# connectors.net
KiCad netlist of a schematic drawn in EAGLE
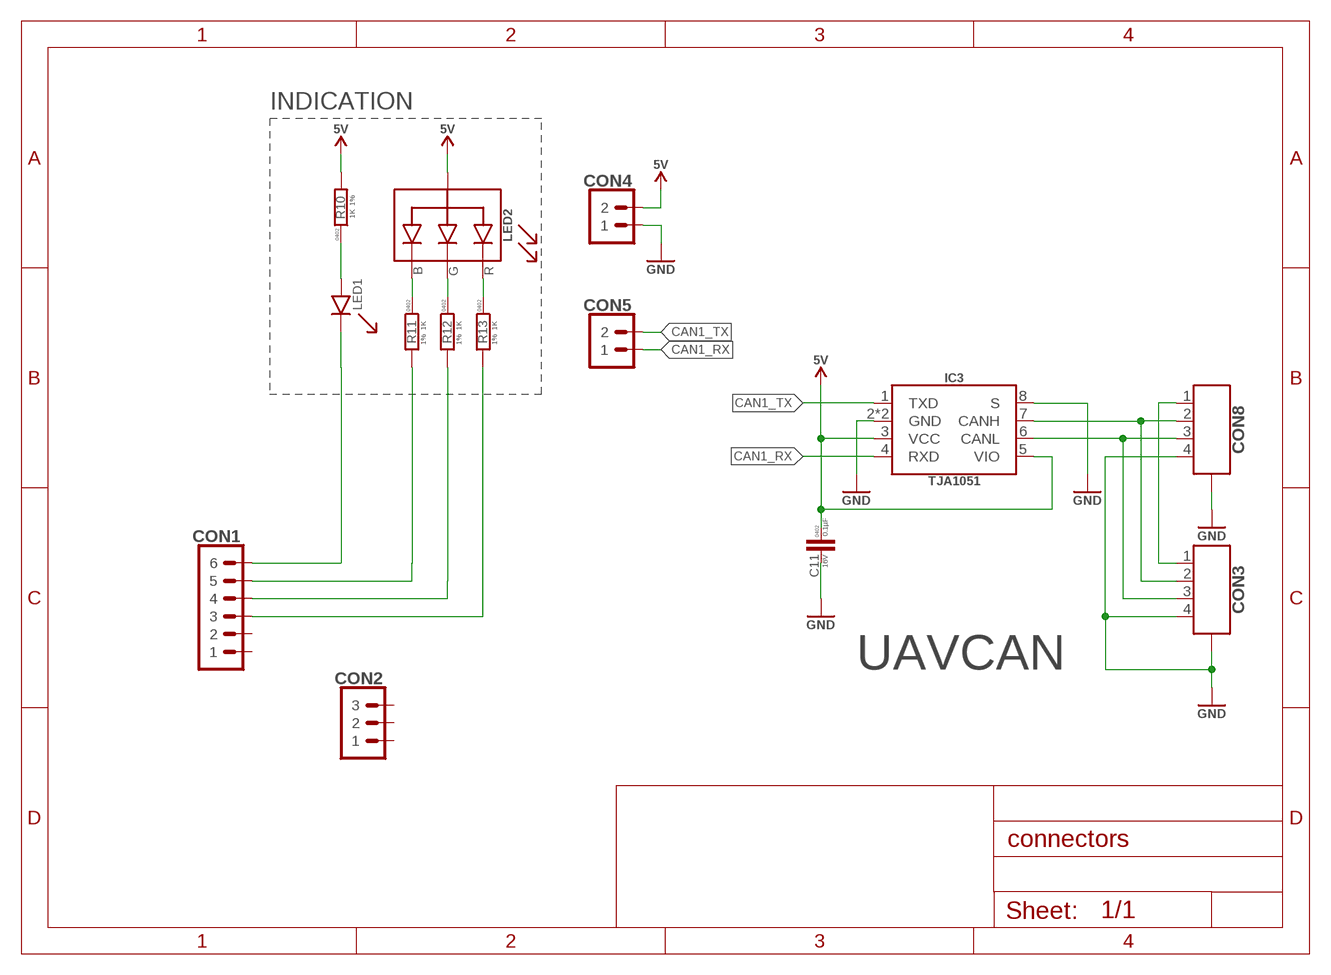
[diagram p0: schematic, sheet 1]

(export (version "E")
  (design (tool "Eeschema 10.0.6"))
  (components
    (comp (ref "C11")
      (value "0.1µF")
      (footprint "eagle-import:C0402")
      (fields
        (field (name "MANF") "Murata Electronics North America")
        (field (name "PACKAGE") "0402")
        (field (name "TOLERANCE") "+-10%")
        (field (name "VOLTAGE") "16V")
      )
      (libsource (lib "eagle-import") (part "0.1µF-0402-16V_10%_X7R"))
    )
    (comp (ref "CON1")
      (value "PINHEAD_1X06-2")
      (footprint "eagle-import:1X06-PTH-2")
      (libsource (lib "eagle-import") (part "PINHEAD_1X06-2"))
    )
    (comp (ref "CON2")
      (value "PINHEAD_1X03-2.54-RA")
      (footprint "eagle-import:1X03-PTH-2.54-RA")
      (libsource (lib "eagle-import") (part "PINHEAD_1X03-2.54-RA"))
    )
    (comp (ref "CON3")
      (value "CON-4P-JST_GH-RA")
      (footprint "eagle-import:JST_GH-4P-RA")
      (fields (field (name "MANF") "JST Sales America Inc"))
      (libsource (lib "eagle-import") (part "CON-4P-RA-JST_GH"))
    )
    (comp (ref "CON4")
      (value "PINHEAD_1X02-2")
      (footprint "eagle-import:1X02-PTH-2")
      (libsource (lib "eagle-import") (part "PINHEAD_1X02-2"))
    )
    (comp (ref "CON5")
      (value "PINHEAD_1X02-2")
      (footprint "eagle-import:1X02-PTH-2")
      (libsource (lib "eagle-import") (part "PINHEAD_1X02-2"))
    )
    (comp (ref "CON8")
      (value "CON-4P-JST_GH-RA")
      (footprint "eagle-import:JST_GH-4P-RA")
      (fields (field (name "MANF") "JST Sales America Inc"))
      (libsource (lib "eagle-import") (part "CON-4P-RA-JST_GH"))
    )
    (comp (ref "IC3")
      (value "TJA1051")
      (footprint "eagle-import:SOT782-1")
      (fields (field (name "MANF") "NXP Semiconductors"))
      (libsource (lib "eagle-import") (part "TJA1051"))
    )
    (comp (ref "LED1")
      (value "GREEN")
      (footprint "eagle-import:0402_LED")
      (fields (field (name "MANF") "Rohm Semiconductor"))
      (libsource (lib "eagle-import") (part "LED-0402-GREEN"))
    )
    (comp (ref "LED2")
      (value "LTST-C19HE1WT")
      (footprint "eagle-import:LITE_ON_RGB_LED")
      (fields (field (name "MANF") "Lite-On Inc"))
      (libsource (lib "eagle-import") (part "LTST-C19HE1WT"))
    )
    (comp (ref "R10")
      (value "1K")
      (footprint "eagle-import:R0402")
      (fields (field (name "MANF") "Yageo") (field (name "PACKAGE") "0402") (field (name "TOLERANCE") "1%"))
      (libsource (lib "eagle-import") (part "1K-0402-1%"))
    )
    (comp (ref "R11")
      (value "1K")
      (footprint "eagle-import:R0402")
      (fields (field (name "MANF") "Yageo") (field (name "PACKAGE") "0402") (field (name "TOLERANCE") "1%"))
      (libsource (lib "eagle-import") (part "1K-0402-1%"))
    )
    (comp (ref "R12")
      (value "1K")
      (footprint "eagle-import:R0402")
      (fields (field (name "MANF") "Yageo") (field (name "PACKAGE") "0402") (field (name "TOLERANCE") "1%"))
      (libsource (lib "eagle-import") (part "1K-0402-1%"))
    )
    (comp (ref "R13")
      (value "1K")
      (footprint "eagle-import:R0402")
      (fields (field (name "MANF") "Yageo") (field (name "PACKAGE") "0402") (field (name "TOLERANCE") "1%"))
      (libsource (lib "eagle-import") (part "1K-0402-1%"))
    )
  )
  (nets
    (net (code "1") (name "5V") (class "Default")
      (node (ref "C11") (pin "1") (pinfunction "1_1") (pintype "passive"))
      (node (ref "CON4") (pin "2") (pinfunction "2_2") (pintype "passive"))
      (node (ref "IC3") (pin "3") (pinfunction "VCC_3") (pintype "bidirectional"))
      (node (ref "IC3") (pin "5") (pinfunction "VIO_5") (pintype "bidirectional"))
      (node (ref "LED2") (pin "+") (pinfunction "A_+") (pintype "bidirectional"))
      (node (ref "R10") (pin "2") (pinfunction "2_2") (pintype "passive"))
    )
    (net (code "2") (name "CAN1_RX") (class "Default")
      (node (ref "CON5") (pin "1") (pinfunction "1_1") (pintype "passive"))
      (node (ref "IC3") (pin "4") (pinfunction "RXD_4") (pintype "bidirectional"))
    )
    (net (code "3") (name "CAN1_TX") (class "Default")
      (node (ref "CON5") (pin "2") (pinfunction "2_2") (pintype "passive"))
      (node (ref "IC3") (pin "1") (pinfunction "TXD_1") (pintype "bidirectional"))
    )
    (net (code "4") (name "GND") (class "Default")
      (node (ref "C11") (pin "2") (pinfunction "2_2") (pintype "passive"))
      (node (ref "CON3") (pin "4") (pinfunction "4_4") (pintype "bidirectional"))
      (node (ref "CON3") (pin "M$0") (pinfunction "GND_M$0") (pintype "bidirectional"))
      (node (ref "CON3") (pin "M$1") (pinfunction "GND_M$1") (pintype "bidirectional"))
      (node (ref "CON4") (pin "1") (pinfunction "1_1") (pintype "passive"))
      (node (ref "CON8") (pin "4") (pinfunction "4_4") (pintype "bidirectional"))
      (node (ref "CON8") (pin "M$0") (pinfunction "GND_M$0") (pintype "bidirectional"))
      (node (ref "CON8") (pin "M$1") (pinfunction "GND_M$1") (pintype "bidirectional"))
      (node (ref "IC3") (pin "2") (pinfunction "GND_2") (pintype "bidirectional"))
      (node (ref "IC3") (pin "8") (pinfunction "S_8") (pintype "bidirectional"))
      (node (ref "IC3") (pin "PAD") (pinfunction "GND_PAD") (pintype "bidirectional"))
    )
    (net (code "5") (name "Net-(CON1-Pad3)") (class "Default")
      (node (ref "CON1") (pin "3") (pinfunction "3_3") (pintype "passive"))
      (node (ref "R13") (pin "2") (pinfunction "2_2") (pintype "passive"))
    )
    (net (code "6") (name "Net-(CON1-Pad4)") (class "Default")
      (node (ref "CON1") (pin "4") (pinfunction "4_4") (pintype "passive"))
      (node (ref "R12") (pin "2") (pinfunction "2_2") (pintype "passive"))
    )
    (net (code "7") (name "Net-(CON1-Pad5)") (class "Default")
      (node (ref "CON1") (pin "5") (pinfunction "5_5") (pintype "passive"))
      (node (ref "R11") (pin "2") (pinfunction "2_2") (pintype "passive"))
    )
    (net (code "8") (name "Net-(CON1-Pad6)") (class "Default")
      (node (ref "CON1") (pin "6") (pinfunction "6_6") (pintype "passive"))
      (node (ref "LED1") (pin "C") (pinfunction "C_C") (pintype "bidirectional"))
    )
    (net (code "9") (name "Net-(CON3-Pad1)") (class "Default")
      (node (ref "CON3") (pin "1") (pinfunction "1_1") (pintype "bidirectional"))
      (node (ref "CON8") (pin "1") (pinfunction "1_1") (pintype "bidirectional"))
    )
    (net (code "10") (name "Net-(IC3-CANH)") (class "Default")
      (node (ref "CON3") (pin "2") (pinfunction "2_2") (pintype "bidirectional"))
      (node (ref "CON8") (pin "2") (pinfunction "2_2") (pintype "bidirectional"))
      (node (ref "IC3") (pin "7") (pinfunction "CANH_7") (pintype "bidirectional"))
    )
    (net (code "11") (name "Net-(IC3-CANL)") (class "Default")
      (node (ref "CON3") (pin "3") (pinfunction "3_3") (pintype "bidirectional"))
      (node (ref "CON8") (pin "3") (pinfunction "3_3") (pintype "bidirectional"))
      (node (ref "IC3") (pin "6") (pinfunction "CANL_6") (pintype "bidirectional"))
    )
    (net (code "12") (name "Net-(LED1-PadA)") (class "Default")
      (node (ref "LED1") (pin "A") (pinfunction "A_A") (pintype "bidirectional"))
      (node (ref "R10") (pin "1") (pinfunction "1_1") (pintype "passive"))
    )
    (net (code "13") (name "Net-(LED2-PadB)") (class "Default")
      (node (ref "LED2") (pin "B") (pinfunction "B_B") (pintype "bidirectional"))
      (node (ref "R11") (pin "1") (pinfunction "1_1") (pintype "passive"))
    )
    (net (code "14") (name "Net-(LED2-PadG)") (class "Default")
      (node (ref "LED2") (pin "G") (pinfunction "G_G") (pintype "bidirectional"))
      (node (ref "R12") (pin "1") (pinfunction "1_1") (pintype "passive"))
    )
    (net (code "15") (name "Net-(LED2-PadR)") (class "Default")
      (node (ref "LED2") (pin "R") (pinfunction "R_R") (pintype "bidirectional"))
      (node (ref "R13") (pin "1") (pinfunction "1_1") (pintype "passive"))
    )
    (net (code "16") (name "unconnected-(CON1-Pad1)") (class "Default")
      (node (ref "CON1") (pin "1") (pinfunction "1_1") (pintype "passive"))
    )
    (net (code "17") (name "unconnected-(CON1-Pad2)") (class "Default")
      (node (ref "CON1") (pin "2") (pinfunction "2_2") (pintype "passive"))
    )
    (net (code "18") (name "unconnected-(CON2-Pad1)") (class "Default")
      (node (ref "CON2") (pin "1") (pinfunction "1_1") (pintype "passive"))
    )
    (net (code "19") (name "unconnected-(CON2-Pad2)") (class "Default")
      (node (ref "CON2") (pin "2") (pinfunction "2_2") (pintype "passive"))
    )
    (net (code "20") (name "unconnected-(CON2-Pad3)") (class "Default")
      (node (ref "CON2") (pin "3") (pinfunction "3_3") (pintype "passive"))
    )
  )
)
